# Isolated_Communication.net
KiCad netlist of a schematic drawn in Altium Designer
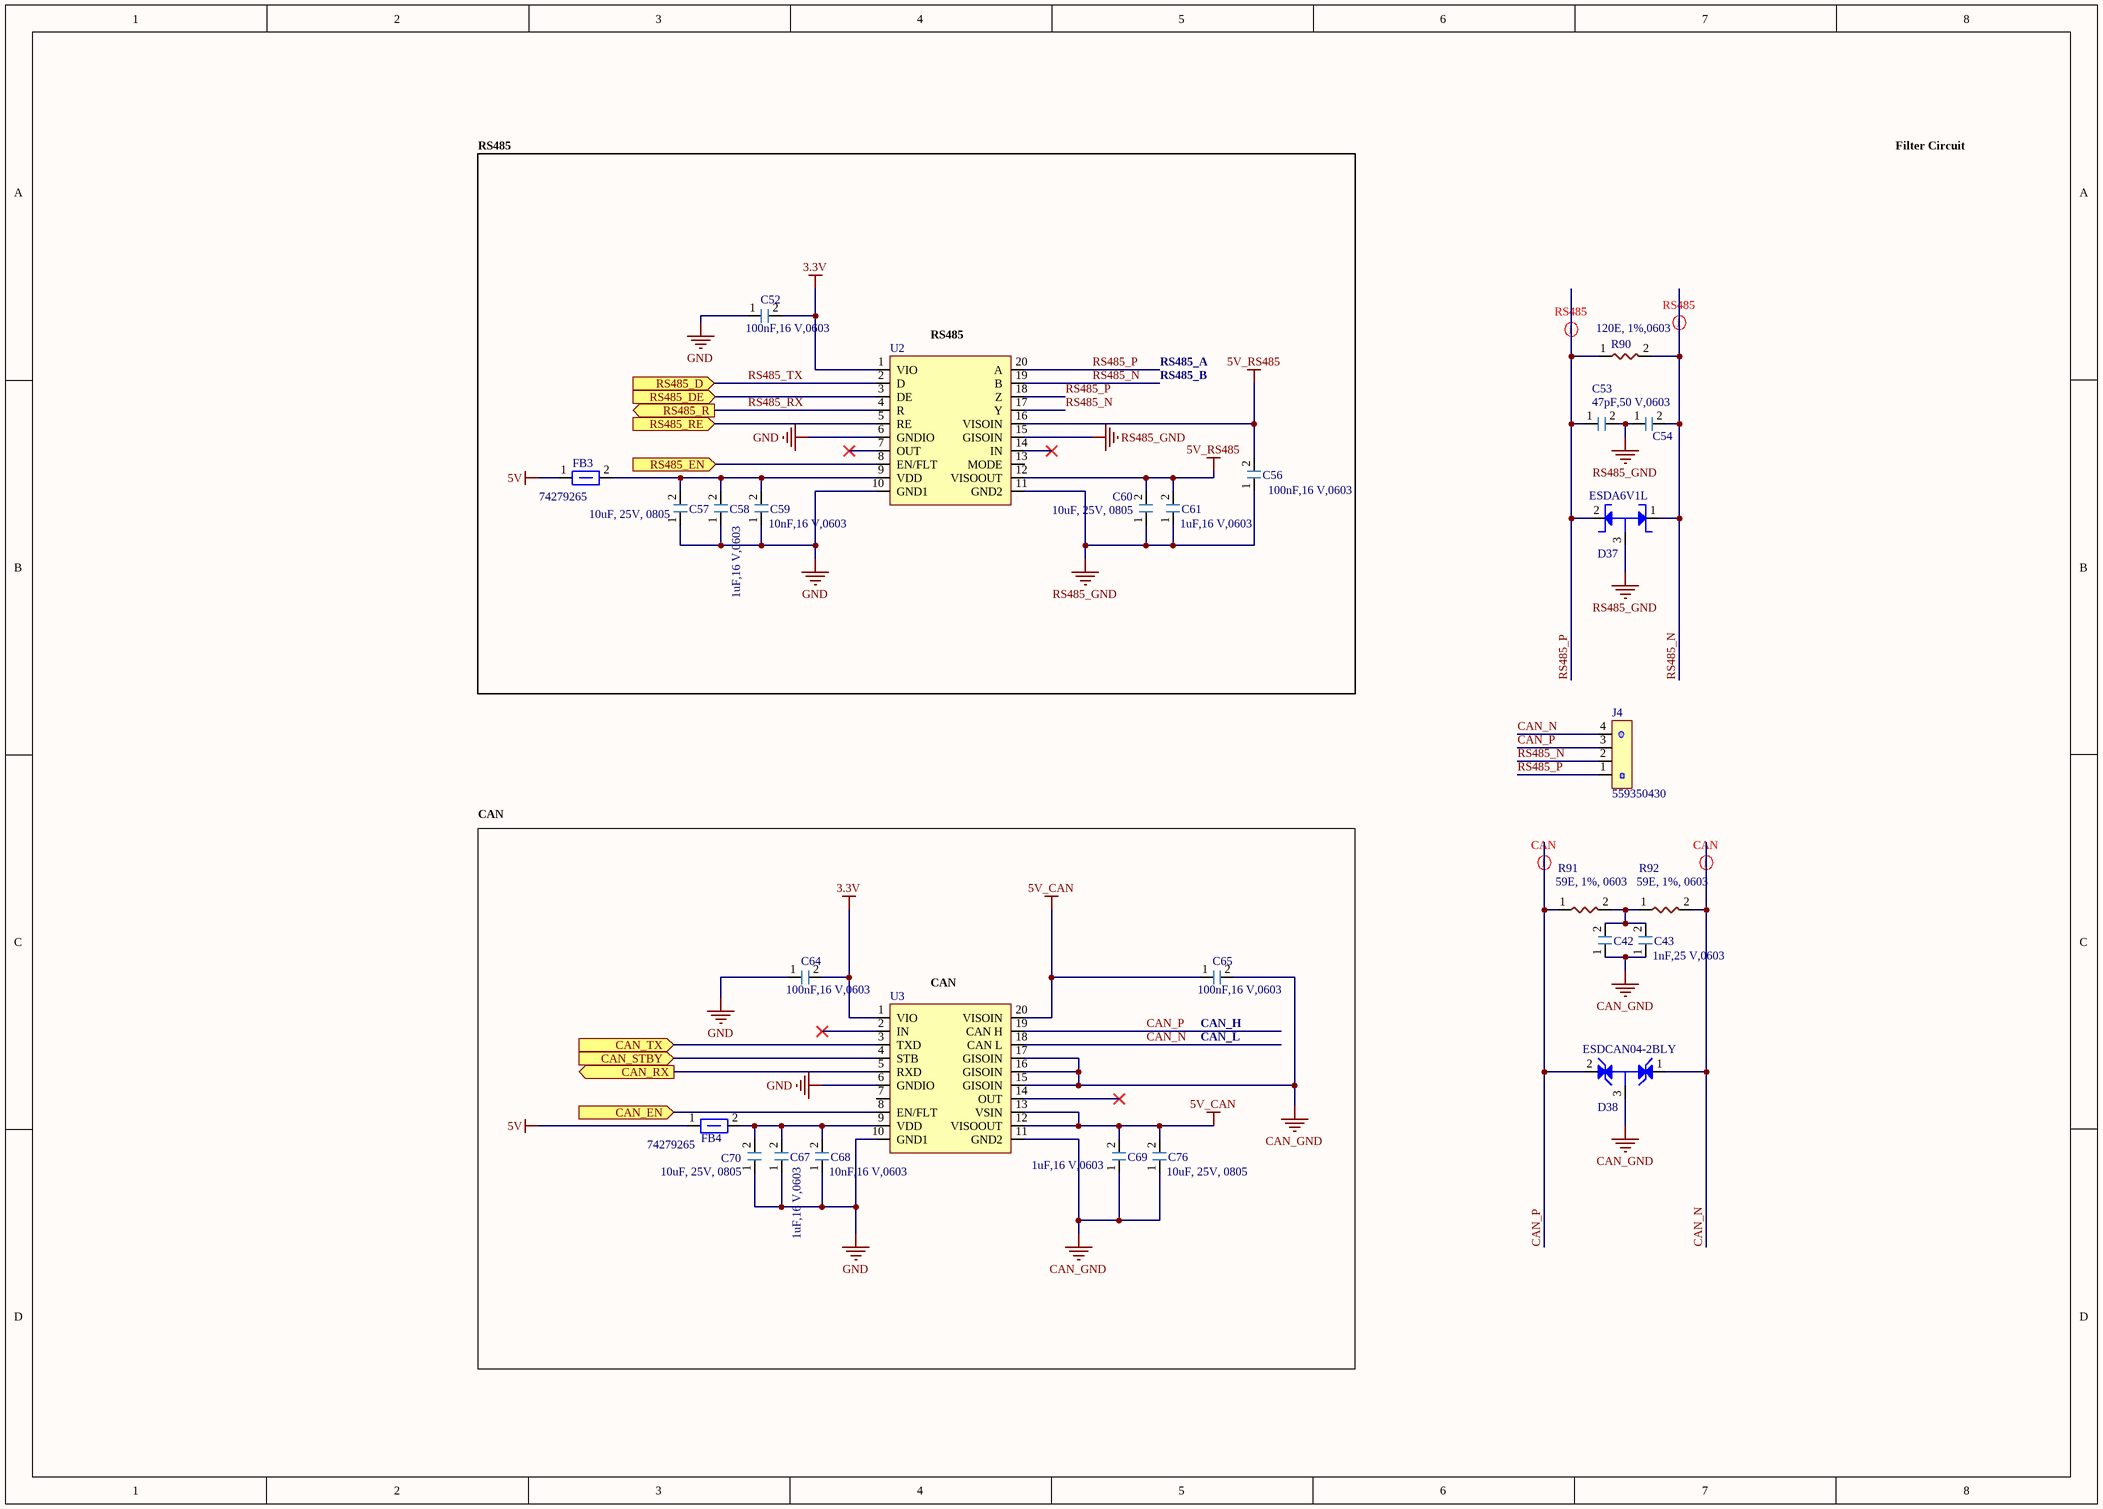
[diagram p0: Isolated Communication.SchDoc]

(export (version "E")
  (design (tool "Eeschema 10.0.6"))
  (components
    (comp (ref "C42")
      (value "C0603C102J3GACAUTO")
      (footprint "BMS_V2.1_Adv:CAPC1608X05N 0603")
      (description "Multilayer Ceramic Capacitor, 1000 pF, 25V, ±5%,  C0G 0603 [1608 Metric]")
      (fields (field (name "MANUFACTURER") "KEMET") (field (name "VOLTAGE") "25V"))
      (libsource (lib "BMS_V2.1_Adv") (part "Cap_C0603C102J3GACAUTO"))
    )
    (comp (ref "C43")
      (value "C0603C102J3GACAUTO")
      (footprint "BMS_V2.1_Adv:CAPC1608X05N 0603")
      (description "Multilayer Ceramic Capacitor, 1000 pF, 25V, ±5%,  C0G 0603 [1608 Metric]")
      (fields
        (field (name "MANUFACTURER") "KEMET")
        (field (name "VOLTAGE") "25V")
        (field (name "VALUE DISPLAY") "1nF,25 V,0603")
      )
      (libsource (lib "BMS_V2.1_Adv") (part "Cap_C0603C102J3GACAUTO"))
    )
    (comp (ref "C52")
      (value "CC0603KRX7R7BB104")
      (footprint "CAPC1608X05N 0603")
      (description "Multilayer Ceramic Capacitor, 100 nF, 16V, ±10%,  X7R 0603 [1608 Metric]")
      (fields
        (field (name "MANUFACTURER") "Yageo")
        (field (name "TOLERANCE") "10%")
        (field (name "VALUE DISPLAY") "100nF,16 V,0603")
      )
      (libsource (lib "BMS_V2.1_Adv") (part "Cap_CC0603KRX7R7BB104"))
    )
    (comp (ref "C53")
      (value "CC0603JRNPO9BN470")
      (footprint "CAPC1608X05N 0603")
      (description "Multilayer Ceramic Capacitor, 47 pF, 50V, ±5%,  C0G 0603 [1608 Metric]")
      (fields
        (field (name "MANUFACTURER") "Yageo")
        (field (name "TOLERANCE") "5%")
        (field (name "VALUE DISPLAY") "47pF,50 V,0603")
      )
      (libsource (lib "BMS_V2.1_Adv") (part "Cap_CC0603JRNPO9BN470"))
    )
    (comp (ref "C54")
      (value "CC0603JRNPO9BN470")
      (footprint "CAPC1608X05N 0603")
      (description "Multilayer Ceramic Capacitor, 47 pF, 50V, ±5%,  C0G 0603 [1608 Metric]")
      (fields (field (name "MANUFACTURER") "Yageo") (field (name "TOLERANCE") "5%"))
      (libsource (lib "BMS_V2.1_Adv") (part "Cap_CC0603JRNPO9BN470"))
    )
    (comp (ref "C56")
      (value "CC0603KRX7R7BB104")
      (footprint "CAPC1608X05N 0603")
      (description "Multilayer Ceramic Capacitor, 100 nF, 16V, ±10%,  X7R 0603 [1608 Metric]")
      (fields
        (field (name "MANUFACTURER") "Yageo")
        (field (name "TOLERANCE") "10%")
        (field (name "VALUE DISPLAY") "100nF,16 V,0603")
      )
      (libsource (lib "BMS_V2.1_Adv") (part "Cap_CC0603KRX7R7BB104"))
    )
    (comp (ref "C57")
      (value "GRM21BZ71E106KE15L")
      (footprint "BMS_V2.1_Adv:CAPC2012X13N 0805")
      (description "Multilayer Ceramic Capacitor, 10 uF, 25V, ±10%,  X7R 0805 (2012 Metric)")
      (fields
        (field (name "MANUFACTURER") "Murata")
        (field (name "TOLERANCE") "10%")
        (field (name "VALUE DISPLAY") "10uF, 25V, 0805")
      )
      (libsource (lib "BMS_V2.1_Adv") (part "Cap_GRM21BZ71E106KE15L"))
    )
    (comp (ref "C58")
      (value "CGA3E1X7R1C105K080AC")
      (footprint "CAPC1608X05N 0603")
      (description "Multilayer Ceramic Capacitor, 1uF, 16V, ±10%,  X7R 0603 [1608 Metric]")
      (fields
        (field (name "MANUFACTURER") "TDK Corporation")
        (field (name "VOLTAGE") "16V")
        (field (name "VALUE DISPLAY") "1uF,16 V,0603")
      )
      (libsource (lib "BMS_V2.1_Adv") (part "Cap_CGA3E1X7R1C105K080AC"))
    )
    (comp (ref "C59")
      (value "C0603C103K4RECTU")
      (footprint "CAPC1608X05N 0603")
      (description "Multilayer Ceramic Capacitor, 10 nF, 16V, ±10%,  X7R 0603 [1608 Metric]")
      (fields
        (field (name "MANUFACTURER") "KEMET")
        (field (name "TOLERANCE") "10%")
        (field (name "VALUE DISPLAY") "10nF,16 V,0603")
      )
      (libsource (lib "BMS_V2.1_Adv") (part "Cap_C0603C103K4RECTU"))
    )
    (comp (ref "C60")
      (value "GRM21BZ71E106KE15L")
      (footprint "BMS_V2.1_Adv:CAPC2012X13N 0805")
      (description "Multilayer Ceramic Capacitor, 10 uF, 25V, ±10%,  X7R 0805 (2012 Metric)")
      (fields
        (field (name "MANUFACTURER") "Murata")
        (field (name "TOLERANCE") "10%")
        (field (name "VALUE DISPLAY") "10uF, 25V, 0805")
      )
      (libsource (lib "BMS_V2.1_Adv") (part "Cap_GRM21BZ71E106KE15L"))
    )
    (comp (ref "C61")
      (value "CGA3E1X7R1C105K080AC")
      (footprint "CAPC1608X05N 0603")
      (description "Multilayer Ceramic Capacitor, 1uF, 16V, ±10%,  X7R 0603 [1608 Metric]")
      (fields
        (field (name "MANUFACTURER") "TDK Corporation")
        (field (name "VOLTAGE") "16V")
        (field (name "VALUE DISPLAY") "1uF,16 V,0603")
      )
      (libsource (lib "BMS_V2.1_Adv") (part "Cap_CGA3E1X7R1C105K080AC"))
    )
    (comp (ref "C64")
      (value "CC0603KRX7R7BB104")
      (footprint "CAPC1608X05N 0603")
      (description "Multilayer Ceramic Capacitor, 100 nF, 16V, ±10%,  X7R 0603 [1608 Metric]")
      (fields
        (field (name "MANUFACTURER") "Yageo")
        (field (name "TOLERANCE") "10%")
        (field (name "VALUE DISPLAY") "100nF,16 V,0603")
      )
      (libsource (lib "BMS_V2.1_Adv") (part "Cap_CC0603KRX7R7BB104"))
    )
    (comp (ref "C65")
      (value "CC0603KRX7R7BB104")
      (footprint "CAPC1608X05N 0603")
      (description "Multilayer Ceramic Capacitor, 100 nF, 16V, ±10%,  X7R 0603 [1608 Metric]")
      (fields
        (field (name "MANUFACTURER") "Yageo")
        (field (name "TOLERANCE") "10%")
        (field (name "VALUE DISPLAY") "100nF,16 V,0603")
      )
      (libsource (lib "BMS_V2.1_Adv") (part "Cap_CC0603KRX7R7BB104"))
    )
    (comp (ref "C67")
      (value "CGA3E1X7R1C105K080AC")
      (footprint "CAPC1608X05N 0603")
      (description "Multilayer Ceramic Capacitor, 1uF, 16V, ±10%,  X7R 0603 [1608 Metric]")
      (fields
        (field (name "MANUFACTURER") "TDK Corporation")
        (field (name "VOLTAGE") "16V")
        (field (name "VALUE DISPLAY") "1uF,16 V,0603")
      )
      (libsource (lib "BMS_V2.1_Adv") (part "Cap_CGA3E1X7R1C105K080AC"))
    )
    (comp (ref "C68")
      (value "C0603C103K4RECTU")
      (footprint "CAPC1608X05N 0603")
      (description "Multilayer Ceramic Capacitor, 10 nF, 16V, ±10%,  X7R 0603 [1608 Metric]")
      (fields
        (field (name "MANUFACTURER") "KEMET")
        (field (name "TOLERANCE") "10%")
        (field (name "VALUE DISPLAY") "10nF,16 V,0603")
      )
      (libsource (lib "BMS_V2.1_Adv") (part "Cap_C0603C103K4RECTU"))
    )
    (comp (ref "C69")
      (value "CGA3E1X7R1C105K080AC")
      (footprint "CAPC1608X05N 0603")
      (description "Multilayer Ceramic Capacitor, 1uF, 16V, ±10%,  X7R 0603 [1608 Metric]")
      (fields
        (field (name "MANUFACTURER") "TDK Corporation")
        (field (name "VOLTAGE") "16V")
        (field (name "VALUE DISPLAY") "1uF,16 V,0603")
      )
      (libsource (lib "BMS_V2.1_Adv") (part "Cap_CGA3E1X7R1C105K080AC"))
    )
    (comp (ref "C70")
      (value "GRM21BZ71E106KE15L")
      (footprint "BMS_V2.1_Adv:CAPC2012X13N 0805")
      (description "Multilayer Ceramic Capacitor, 10 uF, 25V, ±10%,  X7R 0805 (2012 Metric)")
      (fields
        (field (name "MANUFACTURER") "Murata")
        (field (name "TOLERANCE") "10%")
        (field (name "VALUE DISPLAY") "10uF, 25V, 0805")
      )
      (libsource (lib "BMS_V2.1_Adv") (part "Cap_GRM21BZ71E106KE15L"))
    )
    (comp (ref "C76")
      (value "GRM21BZ71E106KE15L")
      (footprint "BMS_V2.1_Adv:CAPC2012X13N 0805")
      (description "Multilayer Ceramic Capacitor, 10 uF, 25V, ±10%,  X7R 0805 (2012 Metric)")
      (fields
        (field (name "MANUFACTURER") "Murata")
        (field (name "TOLERANCE") "10%")
        (field (name "VALUE DISPLAY") "10uF, 25V, 0805")
      )
      (libsource (lib "BMS_V2.1_Adv") (part "Cap_GRM21BZ71E106KE15L"))
    )
    (comp (ref "D37")
      (value "ESDA6V1L")
      (footprint "SOT95P255X140-3N")
      (description "Clamp Ipp Tvs Diode Surface Mount SOT-23-3 Unidirectional")
      (fields
        (field (name "MANUFACTURER") "ST")
        (field (name "POWER") "300W")
        (field (name "VALUE DISPLAY") "ESDA6V1L")
      )
      (libsource (lib "BMS_V2.1_Adv") (part "Diode_TVS_ESDA6V1L"))
    )
    (comp (ref "D38")
      (value "ESDCAN04-2BLY")
      (footprint "SOT95P255X125-3N")
      (description "43V Clamp 3.7A (8/20µs) Ipp Tvs Diode Surface Mount SOT-23-3 Bidirectional")
      (fields
        (field (name "MANUFACTURER") "ST")
        (field (name "POWER") "230W")
        (field (name "VALUE DISPLAY") "ESDCAN04-2BLY")
      )
      (libsource (lib "BMS_V2.1_Adv") (part "Diode_TVS_ESDCAN04-2BLY"))
    )
    (comp (ref "FB3")
      (value "74279265")
      (footprint "RESC1608X05N 0603")
      (description "600 Ohms @ 100 MHz 1 Signal Line Ferrite Bead 0603 (1608 Metric) 200mA 450mOhm")
      (fields
        (field (name "MANUFACTURER") "Wurth Electronik")
        (field (name "MANUFACTURER PART NUMBER") "74279265")
      )
      (libsource (lib "BMS_V2.1_Adv") (part "FB_74279265"))
    )
    (comp (ref "FB4")
      (value "74279265")
      (footprint "RESC1608X05N 0603")
      (description "600 Ohms @ 100 MHz 1 Signal Line Ferrite Bead 0603 (1608 Metric) 200mA 450mOhm")
      (fields (field (name "MANUFACTURER") "Wurth Electronik"))
      (libsource (lib "BMS_V2.1_Adv") (part "FB_74279265"))
    )
    (comp (ref "J4")
      (value "559350430")
      (footprint "BMS_V2.1_Adv:Con_559350430")
      (description "2.00mm Pitch MicroClasp Wire-to-Board Header, Dual Row, Right Angle, 4 Circuits")
      (fields (field (name "CRIMP PART NUMBER") "561349000") (field (name "MANUFACTURER") "Molex"))
      (libsource (lib "BMS_V2.1_Adv") (part "Con_559350430"))
    )
    (comp (ref "R90")
      (value "AF0603FR-07120RL")
      (footprint "RESC1608X05N 0603")
      (fields
        (field (name "MANUFACTURER") "Yageo")
        (field (name "POWER") "1/10W")
        (field (name "TOLERANCE") "1%")
        (field (name "VALUE DISPLAY") "120E, 1%,0603")
      )
      (libsource (lib "BMS_V2.1_Adv") (part "Res_AF0603FR-07120RL"))
    )
    (comp (ref "R91")
      (value "AC0603FR-0759RL")
      (footprint "RESC1608X05N 0603")
      (fields
        (field (name "MANUFACTURER") "Yageo")
        (field (name "POWER") "1/10W")
        (field (name "TOLERANCE") "1%")
        (field (name "VALUE DISPLAY") "59E, 1%, 0603")
      )
      (libsource (lib "BMS_V2.1_Adv") (part "Res_AC0603FR-0759RL"))
    )
    (comp (ref "R92")
      (value "AC0603FR-0759RL")
      (footprint "RESC1608X05N 0603")
      (fields
        (field (name "MANUFACTURER") "Yageo")
        (field (name "POWER") "1/10W")
        (field (name "TOLERANCE") "1%")
        (field (name "VALUE DISPLAY") "59E, 1%, 0603")
      )
      (libsource (lib "BMS_V2.1_Adv") (part "Res_AC0603FR-0759RL"))
    )
    (comp (ref "U2")
      (value "ISOW1412BDFMR")
      (footprint "SOIC127P1030X355-20N")
      (fields (field (name "MANUFACTURER") "Texas Instruments"))
      (libsource (lib "BMS_V2.1_Adv") (part "IC_ISOW1412BDFMR"))
    )
    (comp (ref "U3")
      (value "ISOW1044BDFMR")
      (footprint "SOIC127P1030X355-20N")
      (description "1/1 Transceiver, Isolated Half CANbus 20-SOIC")
      (fields (field (name "MANUFACTURER") "Texas Instruments"))
      (libsource (lib "BMS_V2.1_Adv") (part "IC_ISOW1044BDFMR"))
    )
  )
  (nets
    (net (code "1") (name "/CAN_EN") (class "Default")
      (node (ref "U3") (pin "8") (pinfunction "EN/FLT_8") (pintype "passive"))
    )
    (net (code "2") (name "/CAN_N") (class "Default")
      (node (ref "D38") (pin "1") (pinfunction "Cathode_1") (pintype "passive"))
      (node (ref "J4") (pin "4") (pinfunction "4_4") (pintype "passive"))
      (node (ref "R92") (pin "2") (pinfunction "2_2") (pintype "passive"))
      (node (ref "U3") (pin "18") (pinfunction "CAN_L_18") (pintype "passive"))
    )
    (net (code "3") (name "/CAN_P") (class "Default")
      (node (ref "D38") (pin "2") (pinfunction "Anode_2") (pintype "passive"))
      (node (ref "J4") (pin "3") (pinfunction "3_3") (pintype "passive"))
      (node (ref "R91") (pin "1") (pinfunction "1_1") (pintype "passive"))
      (node (ref "U3") (pin "19") (pinfunction "CAN_H_19") (pintype "passive"))
    )
    (net (code "4") (name "/CAN_RX") (class "Default")
      (node (ref "U3") (pin "5") (pinfunction "RXD_5") (pintype "passive"))
    )
    (net (code "5") (name "/CAN_STBY") (class "Default")
      (node (ref "U3") (pin "4") (pinfunction "STB_4") (pintype "passive"))
    )
    (net (code "6") (name "/CAN_TX") (class "Default")
      (node (ref "U3") (pin "3") (pinfunction "TXD_3") (pintype "passive"))
    )
    (net (code "7") (name "/RS485_DE") (class "Default")
      (node (ref "U2") (pin "3") (pinfunction "DE_3") (pintype "passive"))
    )
    (net (code "8") (name "/RS485_EN") (class "Default")
      (node (ref "U2") (pin "8") (pinfunction "EN/FLT_8") (pintype "passive"))
    )
    (net (code "9") (name "/RS485_N") (class "Default")
      (node (ref "C54") (pin "2") (pinfunction "2_2") (pintype "passive"))
      (node (ref "D37") (pin "1") (pinfunction "Cathode_1") (pintype "passive"))
      (node (ref "J4") (pin "2") (pinfunction "2_2") (pintype "passive"))
      (node (ref "R90") (pin "2") (pinfunction "2_2") (pintype "passive"))
      (node (ref "U2") (pin "17") (pinfunction "Y_17") (pintype "passive"))
      (node (ref "U2") (pin "19") (pinfunction "B_19") (pintype "passive"))
    )
    (net (code "10") (name "/RS485_P") (class "Default")
      (node (ref "C53") (pin "1") (pinfunction "1_1") (pintype "passive"))
      (node (ref "D37") (pin "2") (pinfunction "Cathode_2") (pintype "passive"))
      (node (ref "J4") (pin "1") (pinfunction "1_1") (pintype "passive"))
      (node (ref "R90") (pin "1") (pinfunction "1_1") (pintype "passive"))
      (node (ref "U2") (pin "18") (pinfunction "Z_18") (pintype "passive"))
      (node (ref "U2") (pin "20") (pinfunction "A_20") (pintype "passive"))
    )
    (net (code "11") (name "/RS485_RE") (class "Default")
      (node (ref "U2") (pin "5") (pinfunction "RE_5") (pintype "passive"))
    )
    (net (code "12") (name "/RS485_RX") (class "Default")
      (node (ref "U2") (pin "4") (pinfunction "R_4") (pintype "passive"))
    )
    (net (code "13") (name "/RS485_TX") (class "Default")
      (node (ref "U2") (pin "2") (pinfunction "D_2") (pintype "passive"))
    )
    (net (code "14") (name "3.3V") (class "Default")
      (node (ref "C52") (pin "2") (pinfunction "2_2") (pintype "passive"))
      (node (ref "C64") (pin "2") (pinfunction "2_2") (pintype "passive"))
      (node (ref "U2") (pin "1") (pinfunction "VIO_1") (pintype "passive"))
      (node (ref "U3") (pin "1") (pinfunction "VIO_1") (pintype "passive"))
    )
    (net (code "15") (name "5V") (class "Default")
      (node (ref "FB3") (pin "1") (pinfunction "1_1") (pintype "passive"))
      (node (ref "FB4") (pin "1") (pinfunction "1_1") (pintype "passive"))
    )
    (net (code "16") (name "5V_CAN") (class "Default")
      (node (ref "C65") (pin "1") (pinfunction "1_1") (pintype "passive"))
      (node (ref "C69") (pin "2") (pinfunction "2_2") (pintype "passive"))
      (node (ref "C76") (pin "2") (pinfunction "2_2") (pintype "passive"))
      (node (ref "U3") (pin "12") (pinfunction "VISOOUT_12") (pintype "passive"))
      (node (ref "U3") (pin "13") (pinfunction "VSIN_13") (pintype "passive"))
      (node (ref "U3") (pin "20") (pinfunction "VISOIN_20") (pintype "passive"))
    )
    (net (code "17") (name "5V_RS485") (class "Default")
      (node (ref "C56") (pin "2") (pinfunction "2_2") (pintype "passive"))
      (node (ref "C60") (pin "2") (pinfunction "2_2") (pintype "passive"))
      (node (ref "C61") (pin "2") (pinfunction "2_2") (pintype "passive"))
      (node (ref "U2") (pin "12") (pinfunction "VISOOUT_12") (pintype "passive"))
      (node (ref "U2") (pin "16") (pinfunction "VISOIN_16") (pintype "passive"))
    )
    (net (code "18") (name "CAN_GND") (class "Default")
      (node (ref "C42") (pin "1") (pinfunction "1_1") (pintype "passive"))
      (node (ref "C43") (pin "1") (pinfunction "1_1") (pintype "passive"))
      (node (ref "C65") (pin "2") (pinfunction "2_2") (pintype "passive"))
      (node (ref "C69") (pin "1") (pinfunction "1_1") (pintype "passive"))
      (node (ref "C76") (pin "1") (pinfunction "1_1") (pintype "passive"))
      (node (ref "D38") (pin "3") (pinfunction "3_3") (pintype "passive"))
      (node (ref "U3") (pin "11") (pinfunction "GND2_11") (pintype "passive"))
      (node (ref "U3") (pin "15") (pinfunction "GISOIN_15") (pintype "passive"))
      (node (ref "U3") (pin "16") (pinfunction "GISOIN_16") (pintype "passive"))
      (node (ref "U3") (pin "17") (pinfunction "GISOIN_17") (pintype "passive"))
    )
    (net (code "19") (name "GND") (class "Default")
      (node (ref "C52") (pin "1") (pinfunction "1_1") (pintype "passive"))
      (node (ref "C57") (pin "1") (pinfunction "1_1") (pintype "passive"))
      (node (ref "C58") (pin "1") (pinfunction "1_1") (pintype "passive"))
      (node (ref "C59") (pin "1") (pinfunction "1_1") (pintype "passive"))
      (node (ref "C64") (pin "1") (pinfunction "1_1") (pintype "passive"))
      (node (ref "C67") (pin "1") (pinfunction "1_1") (pintype "passive"))
      (node (ref "C68") (pin "1") (pinfunction "1_1") (pintype "passive"))
      (node (ref "C70") (pin "1") (pinfunction "1_1") (pintype "passive"))
      (node (ref "U2") (pin "10") (pinfunction "GND1_10") (pintype "passive"))
      (node (ref "U2") (pin "6") (pinfunction "GNDIO_6") (pintype "passive"))
      (node (ref "U3") (pin "10") (pinfunction "GND1_10") (pintype "passive"))
      (node (ref "U3") (pin "6") (pinfunction "GNDIO_6") (pintype "passive"))
    )
    (net (code "20") (name "Net-(C42-Pad2)") (class "Default")
      (node (ref "C42") (pin "2") (pinfunction "2_2") (pintype "passive"))
      (node (ref "C43") (pin "2") (pinfunction "2_2") (pintype "passive"))
      (node (ref "R91") (pin "2") (pinfunction "2_2") (pintype "passive"))
      (node (ref "R92") (pin "1") (pinfunction "1_1") (pintype "passive"))
    )
    (net (code "21") (name "Net-(U2-VDD)") (class "Default")
      (node (ref "C57") (pin "2") (pinfunction "2_2") (pintype "passive"))
      (node (ref "C58") (pin "2") (pinfunction "2_2") (pintype "passive"))
      (node (ref "C59") (pin "2") (pinfunction "2_2") (pintype "passive"))
      (node (ref "FB3") (pin "2") (pinfunction "2_2") (pintype "passive"))
      (node (ref "U2") (pin "9") (pinfunction "VDD_9") (pintype "passive"))
    )
    (net (code "22") (name "Net-(U3-VDD)") (class "Default")
      (node (ref "C67") (pin "2") (pinfunction "2_2") (pintype "passive"))
      (node (ref "C68") (pin "2") (pinfunction "2_2") (pintype "passive"))
      (node (ref "C70") (pin "2") (pinfunction "2_2") (pintype "passive"))
      (node (ref "FB4") (pin "2") (pinfunction "2_2") (pintype "passive"))
      (node (ref "U3") (pin "9") (pinfunction "VDD_9") (pintype "passive"))
    )
    (net (code "23") (name "RS485_GND") (class "Default")
      (node (ref "C53") (pin "2") (pinfunction "2_2") (pintype "passive"))
      (node (ref "C54") (pin "1") (pinfunction "1_1") (pintype "passive"))
      (node (ref "C56") (pin "1") (pinfunction "1_1") (pintype "passive"))
      (node (ref "C60") (pin "1") (pinfunction "1_1") (pintype "passive"))
      (node (ref "C61") (pin "1") (pinfunction "1_1") (pintype "passive"))
      (node (ref "D37") (pin "3") (pinfunction "Anode_3") (pintype "passive"))
      (node (ref "U2") (pin "11") (pinfunction "GND2_11") (pintype "passive"))
      (node (ref "U2") (pin "15") (pinfunction "GISOIN_15") (pintype "passive"))
    )
    (net (code "24") (name "unconnected-(U2-IN-Pad14)") (class "Default")
      (node (ref "U2") (pin "14") (pinfunction "IN_14") (pintype "passive+no_connect"))
    )
    (net (code "25") (name "unconnected-(U2-MODE-Pad13)") (class "Default")
      (node (ref "U2") (pin "13") (pinfunction "MODE_13") (pintype "passive"))
    )
    (net (code "26") (name "unconnected-(U2-OUT-Pad7)") (class "Default")
      (node (ref "U2") (pin "7") (pinfunction "OUT_7") (pintype "passive+no_connect"))
    )
    (net (code "27") (name "unconnected-(U3-IN-Pad2)") (class "Default")
      (node (ref "U3") (pin "2") (pinfunction "IN_2") (pintype "passive+no_connect"))
    )
    (net (code "28") (name "unconnected-(U3-OUT-Pad14)") (class "Default")
      (node (ref "U3") (pin "14") (pinfunction "OUT_14") (pintype "passive+no_connect"))
    )
    (net (code "29") (name "unconnected-(U3-Pad7)") (class "Default")
      (node (ref "U3") (pin "7") (pintype "passive"))
    )
  )
)
